# additionalShield.net
KiCad netlist of a schematic drawn in EAGLE
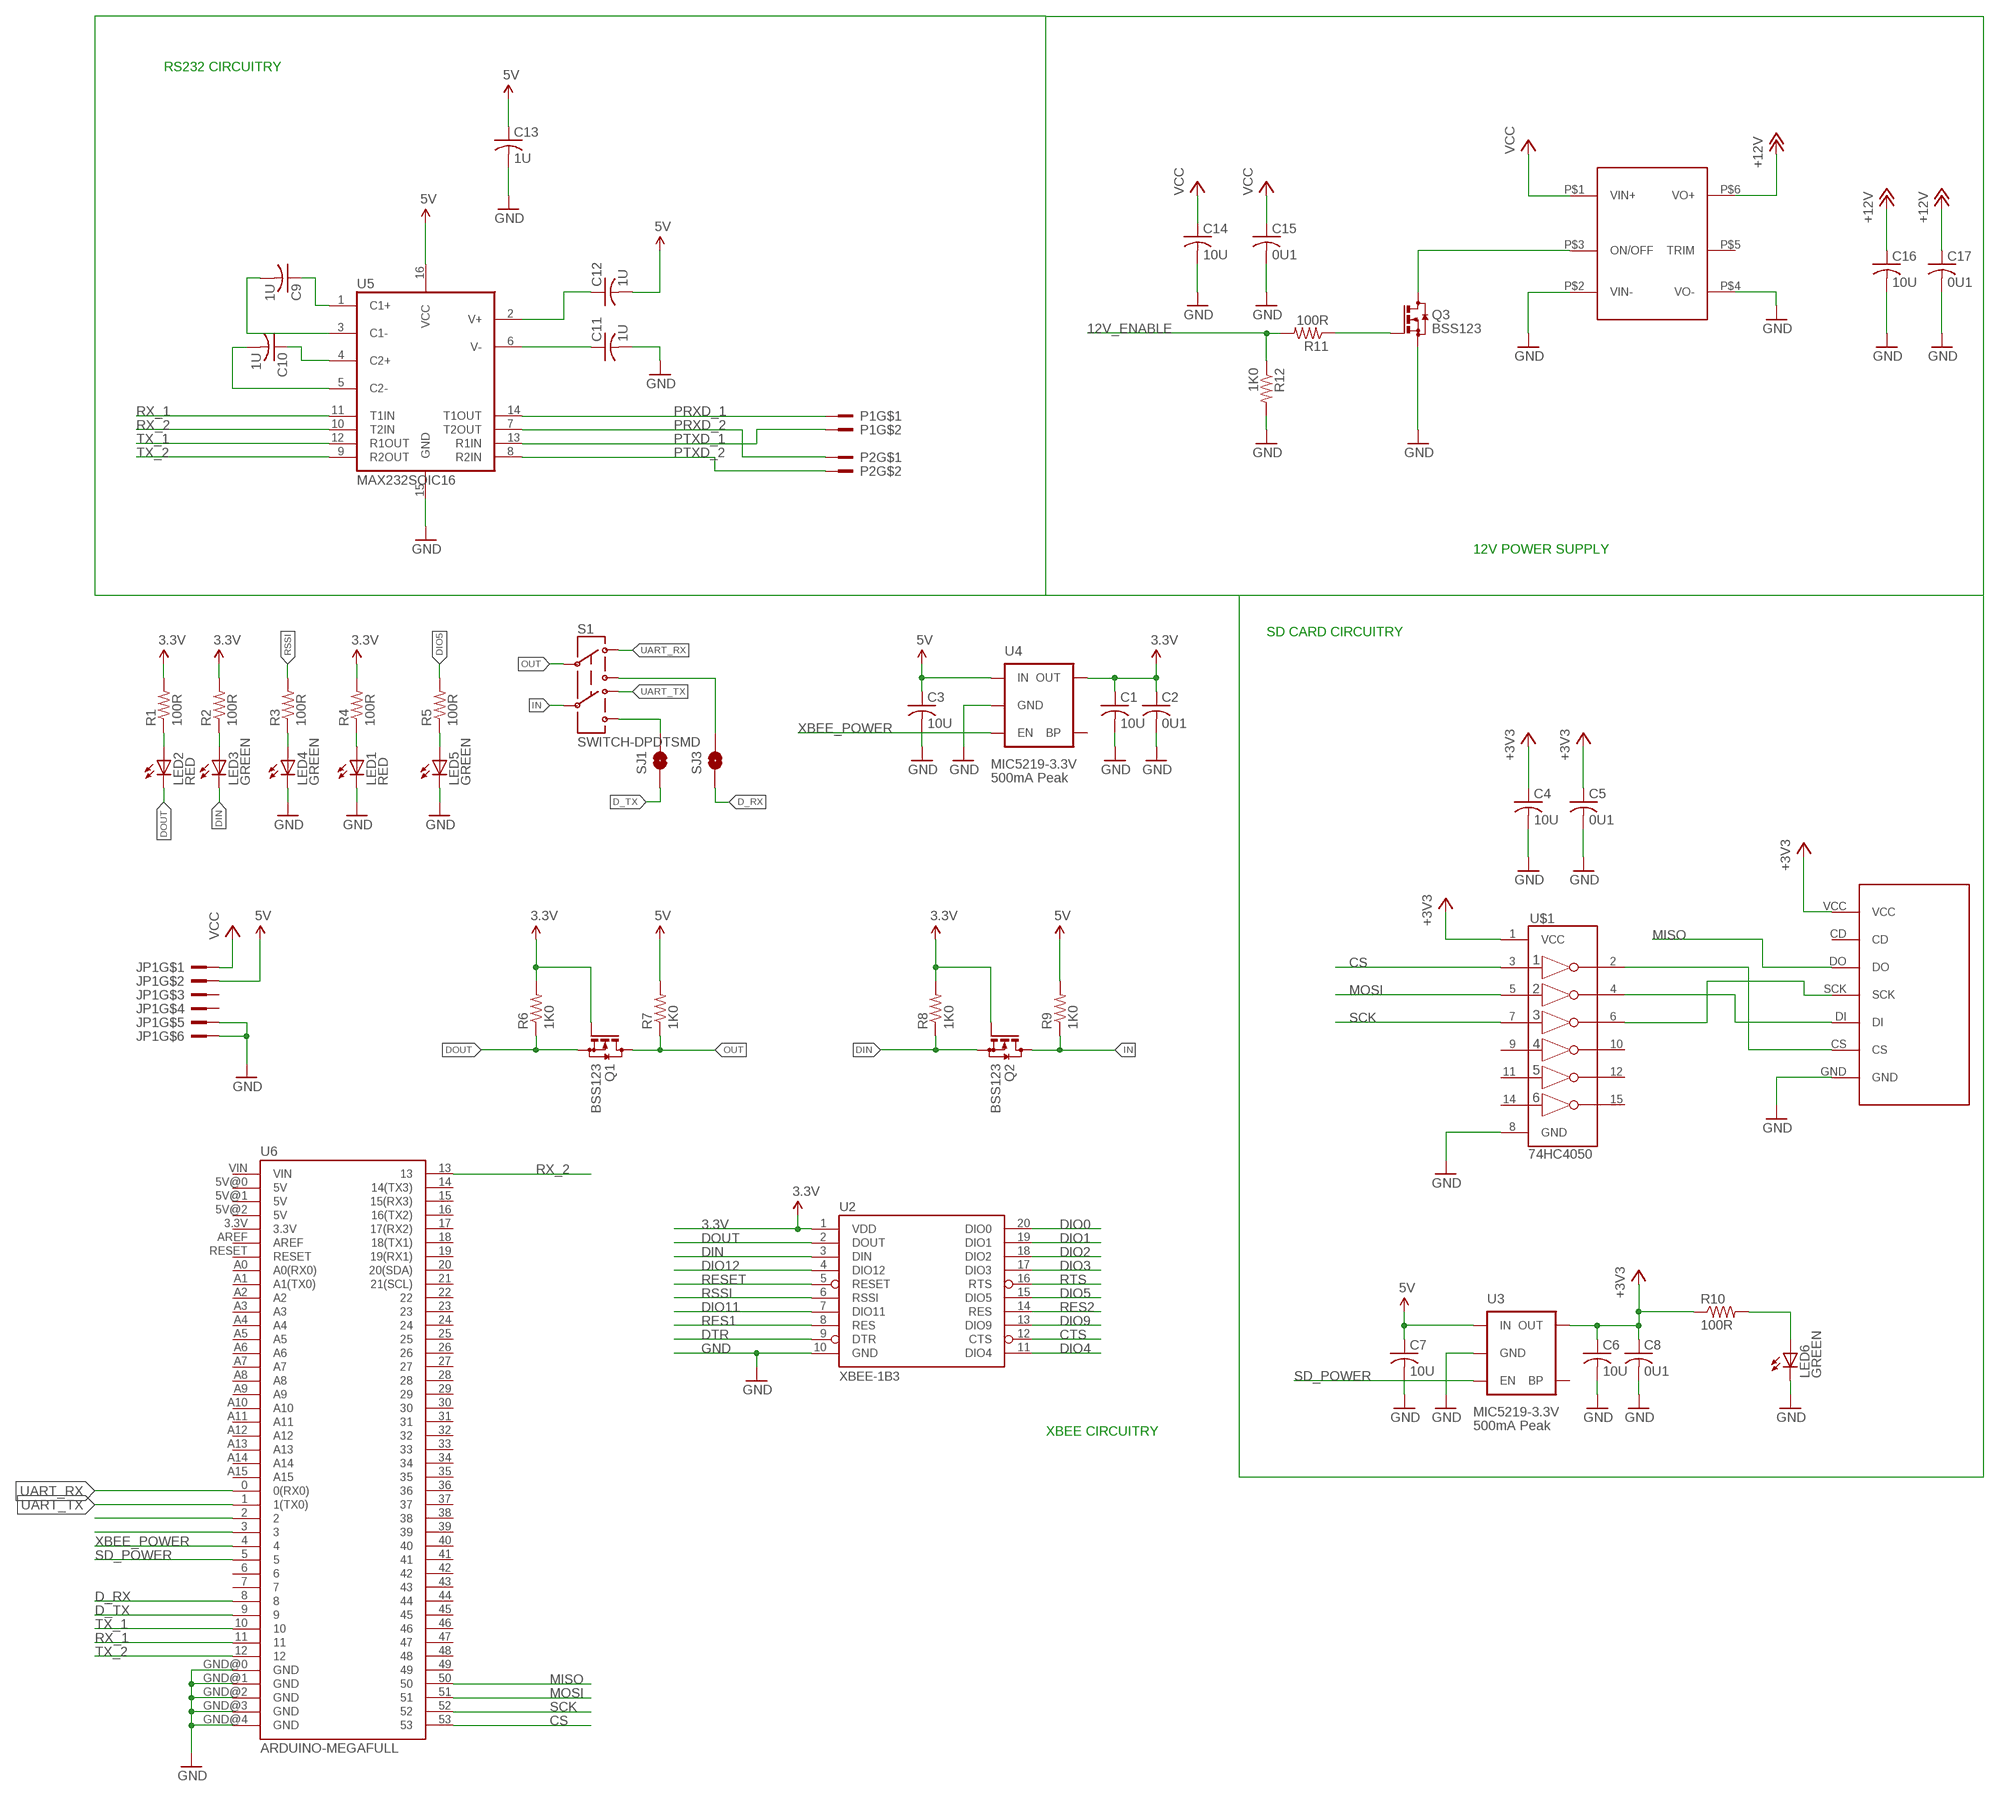
[diagram p0: schematic, sheet 1]

(export (version "E")
  (design (tool "Eeschema 10.0.6"))
  (components
    (comp (ref "C1")
      (value "10U")
      (footprint "eagle-import:C1210K")
      (libsource (lib "eagle-import") (part "C-USC1210K"))
    )
    (comp (ref "C2")
      (value "0U1")
      (footprint "eagle-import:C1210K")
      (libsource (lib "eagle-import") (part "C-USC1210K"))
    )
    (comp (ref "C3")
      (value "10U")
      (footprint "eagle-import:C1210K")
      (libsource (lib "eagle-import") (part "C-USC1210K"))
    )
    (comp (ref "C4")
      (value "10U")
      (footprint "eagle-import:C1210K")
      (libsource (lib "eagle-import") (part "C-USC1210K"))
    )
    (comp (ref "C5")
      (value "0U1")
      (footprint "eagle-import:C1210K")
      (libsource (lib "eagle-import") (part "C-USC1210K"))
    )
    (comp (ref "C6")
      (value "10U")
      (footprint "eagle-import:C1210K")
      (libsource (lib "eagle-import") (part "C-USC1210K"))
    )
    (comp (ref "C7")
      (value "10U")
      (footprint "eagle-import:C1210K")
      (libsource (lib "eagle-import") (part "C-USC1210K"))
    )
    (comp (ref "C8")
      (value "0U1")
      (footprint "eagle-import:C1210K")
      (libsource (lib "eagle-import") (part "C-USC1210K"))
    )
    (comp (ref "C9")
      (value "1U")
      (footprint "eagle-import:C1210K")
      (libsource (lib "eagle-import") (part "C-USC1210K"))
    )
    (comp (ref "C10")
      (value "1U")
      (footprint "eagle-import:C1210K")
      (libsource (lib "eagle-import") (part "C-USC1210K"))
    )
    (comp (ref "C11")
      (value "1U")
      (footprint "eagle-import:C1210K")
      (libsource (lib "eagle-import") (part "C-USC1210K"))
    )
    (comp (ref "C12")
      (value "1U")
      (footprint "eagle-import:C1210K")
      (libsource (lib "eagle-import") (part "C-USC1210K"))
    )
    (comp (ref "C13")
      (value "1U")
      (footprint "eagle-import:C1210K")
      (libsource (lib "eagle-import") (part "C-USC1210K"))
    )
    (comp (ref "C14")
      (value "10U")
      (footprint "eagle-import:C1210K")
      (libsource (lib "eagle-import") (part "C-USC1210K"))
    )
    (comp (ref "C15")
      (value "0U1")
      (footprint "eagle-import:C1210K")
      (libsource (lib "eagle-import") (part "C-USC1210K"))
    )
    (comp (ref "C16")
      (value "10U")
      (footprint "eagle-import:C1210K")
      (libsource (lib "eagle-import") (part "C-USC1210K"))
    )
    (comp (ref "C17")
      (value "0U1")
      (footprint "eagle-import:C1210K")
      (libsource (lib "eagle-import") (part "C-USC1210K"))
    )
    (comp (ref "JP1")
      (value "6PIN2ROWARDUINO")
      (footprint "eagle-import:6PIN2ROWARDUINO")
      (libsource (lib "eagle-import") (part "6PIN2ROWARDUINO"))
    )
    (comp (ref "LED1")
      (value "RED")
      (footprint "eagle-import:CHIPLED_1206")
      (libsource (lib "eagle-import") (part "LEDCHIPLED_1206"))
    )
    (comp (ref "LED2")
      (value "RED")
      (footprint "eagle-import:CHIPLED_1206")
      (libsource (lib "eagle-import") (part "LEDCHIPLED_1206"))
    )
    (comp (ref "LED3")
      (value "GREEN")
      (footprint "eagle-import:CHIPLED_1206")
      (libsource (lib "eagle-import") (part "LEDCHIPLED_1206"))
    )
    (comp (ref "LED4")
      (value "GREEN")
      (footprint "eagle-import:CHIPLED_1206")
      (libsource (lib "eagle-import") (part "LEDCHIPLED_1206"))
    )
    (comp (ref "LED5")
      (value "GREEN")
      (footprint "eagle-import:CHIPLED_1206")
      (libsource (lib "eagle-import") (part "LEDCHIPLED_1206"))
    )
    (comp (ref "LED6")
      (value "GREEN")
      (footprint "eagle-import:CHIPLED_1206")
      (libsource (lib "eagle-import") (part "LEDCHIPLED_1206"))
    )
    (comp (ref "P1")
      (value "DF3A-2P-2DSA")
      (footprint "eagle-import:DF3A-2P-2DSA")
      (libsource (lib "eagle-import") (part "DF3A-2P-2DSA"))
    )
    (comp (ref "P2")
      (value "DF3A-2P-2DSA")
      (footprint "eagle-import:DF3A-2P-2DSA")
      (libsource (lib "eagle-import") (part "DF3A-2P-2DSA"))
    )
    (comp (ref "Q1")
      (value "BSS123")
      (footprint "eagle-import:SOT23")
      (libsource (lib "eagle-import") (part "BSS123"))
    )
    (comp (ref "Q2")
      (value "BSS123")
      (footprint "eagle-import:SOT23")
      (libsource (lib "eagle-import") (part "BSS123"))
    )
    (comp (ref "Q3")
      (value "BSS123")
      (footprint "eagle-import:SOT23")
      (libsource (lib "eagle-import") (part "BSS123"))
    )
    (comp (ref "R1")
      (value "100R")
      (footprint "eagle-import:R1206")
      (libsource (lib "eagle-import") (part "R-US_R1206"))
    )
    (comp (ref "R2")
      (value "100R")
      (footprint "eagle-import:R1206")
      (libsource (lib "eagle-import") (part "R-US_R1206"))
    )
    (comp (ref "R3")
      (value "100R")
      (footprint "eagle-import:R1206")
      (libsource (lib "eagle-import") (part "R-US_R1206"))
    )
    (comp (ref "R4")
      (value "100R")
      (footprint "eagle-import:R1206")
      (libsource (lib "eagle-import") (part "R-US_R1206"))
    )
    (comp (ref "R5")
      (value "100R")
      (footprint "eagle-import:R1206")
      (libsource (lib "eagle-import") (part "R-US_R1206"))
    )
    (comp (ref "R6")
      (value "1K0")
      (footprint "eagle-import:R1206")
      (libsource (lib "eagle-import") (part "R-US_R1206"))
    )
    (comp (ref "R7")
      (value "1K0")
      (footprint "eagle-import:R1206")
      (libsource (lib "eagle-import") (part "R-US_R1206"))
    )
    (comp (ref "R8")
      (value "1K0")
      (footprint "eagle-import:R1206")
      (libsource (lib "eagle-import") (part "R-US_R1206"))
    )
    (comp (ref "R9")
      (value "1K0")
      (footprint "eagle-import:R1206")
      (libsource (lib "eagle-import") (part "R-US_R1206"))
    )
    (comp (ref "R10")
      (value "100R")
      (footprint "eagle-import:R1206")
      (libsource (lib "eagle-import") (part "R-US_R1206"))
    )
    (comp (ref "R11")
      (value "100R")
      (footprint "eagle-import:R1206")
      (libsource (lib "eagle-import") (part "R-US_R1206"))
    )
    (comp (ref "R12")
      (value "1K0")
      (footprint "eagle-import:R1206")
      (libsource (lib "eagle-import") (part "R-US_R1206"))
    )
    (comp (ref "S1")
      (value "SWITCH-DPDTSMD")
      (footprint "eagle-import:AYZ0202")
      (libsource (lib "eagle-import") (part "SWITCH-DPDTSMD"))
    )
    (comp (ref "SJ1")
      (value "D_TX")
      (footprint "eagle-import:SJ_2S")
      (libsource (lib "eagle-import") (part "SOLDERJUMPERNC"))
    )
    (comp (ref "SJ3")
      (value "D_RX")
      (footprint "eagle-import:SJ_2S")
      (libsource (lib "eagle-import") (part "SOLDERJUMPERNC"))
    )
    (comp (ref "U$1")
      (value "74HC4050")
      (footprint "eagle-import:SO16")
      (libsource (lib "eagle-import") (part "74HC4050"))
    )
    (comp (ref "U$5")
      (value "SD_BREAKOUT")
      (footprint "eagle-import:SD_BREAKOUT")
      (libsource (lib "eagle-import") (part "SD_BREAKOUT"))
    )
    (comp (ref "U$11")
      (value "SHHD001A3B41Z")
      (footprint "eagle-import:SHHD001A3B41Z")
      (libsource (lib "eagle-import") (part "SHHD001A3B41Z"))
    )
    (comp (ref "U2")
      (value "XBEE-1B3")
      (footprint "eagle-import:XBEE-SMD")
      (libsource (lib "eagle-import") (part "XBEE-1B3"))
    )
    (comp (ref "U3")
      (value "V_REG_LDOSMD")
      (footprint "eagle-import:SOT23-5")
      (libsource (lib "eagle-import") (part "V_REG_LDOSMD"))
    )
    (comp (ref "U4")
      (value "V_REG_LDOSMD")
      (footprint "eagle-import:SOT23-5")
      (libsource (lib "eagle-import") (part "V_REG_LDOSMD"))
    )
    (comp (ref "U5")
      (value "MAX232SOIC16")
      (footprint "eagle-import:SO016")
      (libsource (lib "eagle-import") (part "MAX232SOIC16"))
    )
    (comp (ref "U6")
      (value "ARDUINO-MEGAFULL")
      (footprint "eagle-import:ARDUINO_MEGA")
      (libsource (lib "eagle-import") (part "ARDUINO-MEGAFULL"))
    )
  )
  (nets
    (net (code "1") (name "+3V3") (class "Default")
      (node (ref "C4") (pin "1") (pinfunction "1_1") (pintype "passive"))
      (node (ref "C5") (pin "1") (pinfunction "1_1") (pintype "passive"))
      (node (ref "C6") (pin "1") (pinfunction "1_1") (pintype "passive"))
      (node (ref "C8") (pin "1") (pinfunction "1_1") (pintype "passive"))
      (node (ref "R10") (pin "1") (pinfunction "1_1") (pintype "passive"))
      (node (ref "U$1") (pin "1") (pinfunction "VCC_1") (pintype "power_in"))
      (node (ref "U$5") (pin "VCC") (pinfunction "VCC_VCC") (pintype "bidirectional"))
      (node (ref "U3") (pin "5") (pinfunction "OUT_5") (pintype "passive"))
    )
    (net (code "2") (name "+12V") (class "Default")
      (node (ref "C16") (pin "1") (pinfunction "1_1") (pintype "passive"))
      (node (ref "C17") (pin "1") (pinfunction "1_1") (pintype "passive"))
      (node (ref "U$11") (pin "P$6") (pinfunction "VO+_P$6") (pintype "bidirectional"))
    )
    (net (code "3") (name "/12V_ENABLE") (class "Default")
      (node (ref "R11") (pin "2") (pinfunction "2_2") (pintype "passive"))
      (node (ref "R12") (pin "1") (pinfunction "1_1") (pintype "passive"))
    )
    (net (code "4") (name "/CS") (class "Default")
      (node (ref "U$1") (pin "3") (pinfunction "1A_3") (pintype "input"))
      (node (ref "U6") (pin "53") (pinfunction "53_53") (pintype "bidirectional"))
    )
    (net (code "5") (name "/CTS") (class "Default")
      (node (ref "U2") (pin "12") (pinfunction "CTS_12") (pintype "output"))
    )
    (net (code "6") (name "/DIO0") (class "Default")
      (node (ref "U2") (pin "20") (pinfunction "DIO0_20") (pintype "bidirectional"))
    )
    (net (code "7") (name "/DIO1") (class "Default")
      (node (ref "U2") (pin "19") (pinfunction "DIO1_19") (pintype "bidirectional"))
    )
    (net (code "8") (name "/DIO2") (class "Default")
      (node (ref "U2") (pin "18") (pinfunction "DIO2_18") (pintype "bidirectional"))
    )
    (net (code "9") (name "/DIO3") (class "Default")
      (node (ref "U2") (pin "17") (pinfunction "DIO3_17") (pintype "bidirectional"))
    )
    (net (code "10") (name "/DIO4") (class "Default")
      (node (ref "U2") (pin "11") (pinfunction "DIO4_11") (pintype "bidirectional"))
    )
    (net (code "11") (name "/DIO9") (class "Default")
      (node (ref "U2") (pin "13") (pinfunction "DIO9_13") (pintype "bidirectional"))
    )
    (net (code "12") (name "/DIO11") (class "Default")
      (node (ref "U2") (pin "7") (pinfunction "DIO11_7") (pintype "bidirectional"))
    )
    (net (code "13") (name "/DIO12") (class "Default")
      (node (ref "U2") (pin "4") (pinfunction "DIO12_4") (pintype "bidirectional"))
    )
    (net (code "14") (name "/DTR") (class "Default")
      (node (ref "U2") (pin "9") (pinfunction "DTR_9") (pintype "bidirectional"))
    )
    (net (code "15") (name "/MISO") (class "Default")
      (node (ref "U$5") (pin "DO") (pinfunction "DO_DO") (pintype "bidirectional"))
      (node (ref "U6") (pin "50") (pinfunction "50_50") (pintype "bidirectional"))
    )
    (net (code "16") (name "/MOSI") (class "Default")
      (node (ref "U$1") (pin "5") (pinfunction "2A_5") (pintype "input"))
      (node (ref "U6") (pin "51") (pinfunction "51_51") (pintype "bidirectional"))
    )
    (net (code "17") (name "/PRXD_1") (class "Default")
      (node (ref "P1") (pin "P$1") (pinfunction "KL_P$1") (pintype "passive"))
      (node (ref "U5") (pin "14") (pinfunction "T1OUT_14") (pintype "output"))
    )
    (net (code "18") (name "/PRXD_2") (class "Default")
      (node (ref "P2") (pin "P$1") (pinfunction "KL_P$1") (pintype "passive"))
      (node (ref "U5") (pin "7") (pinfunction "T2OUT_7") (pintype "output"))
    )
    (net (code "19") (name "/PTXD_1") (class "Default")
      (node (ref "P1") (pin "P$2") (pinfunction "KL_P$2") (pintype "passive"))
      (node (ref "U5") (pin "13") (pinfunction "R1IN_13") (pintype "input"))
    )
    (net (code "20") (name "/PTXD_2") (class "Default")
      (node (ref "P2") (pin "P$2") (pinfunction "KL_P$2") (pintype "passive"))
      (node (ref "U5") (pin "8") (pinfunction "R2IN_8") (pintype "input"))
    )
    (net (code "21") (name "/RES1") (class "Default")
      (node (ref "U2") (pin "8") (pinfunction "RES_8") (pintype "bidirectional"))
    )
    (net (code "22") (name "/RES2") (class "Default")
      (node (ref "U2") (pin "14") (pinfunction "RES_14") (pintype "bidirectional"))
    )
    (net (code "23") (name "/RESET") (class "Default")
      (node (ref "U2") (pin "5") (pinfunction "RESET_5") (pintype "input"))
    )
    (net (code "24") (name "/RTS") (class "Default")
      (node (ref "U2") (pin "16") (pinfunction "RTS_16") (pintype "input"))
    )
    (net (code "25") (name "/RX_1") (class "Default")
      (node (ref "U5") (pin "11") (pinfunction "T1IN_11") (pintype "input"))
      (node (ref "U6") (pin "11") (pinfunction "11_11") (pintype "bidirectional"))
    )
    (net (code "26") (name "/RX_2") (class "Default")
      (node (ref "U5") (pin "10") (pinfunction "T2IN_10") (pintype "input"))
      (node (ref "U6") (pin "13") (pinfunction "13_13") (pintype "bidirectional"))
    )
    (net (code "27") (name "/SCK") (class "Default")
      (node (ref "U$1") (pin "7") (pinfunction "3A_7") (pintype "input"))
      (node (ref "U6") (pin "52") (pinfunction "52_52") (pintype "bidirectional"))
    )
    (net (code "28") (name "/SD_POWER") (class "Default")
      (node (ref "U3") (pin "3") (pinfunction "EN_3") (pintype "input"))
      (node (ref "U6") (pin "5") (pinfunction "5_5") (pintype "bidirectional"))
    )
    (net (code "29") (name "/TX_1") (class "Default")
      (node (ref "U5") (pin "12") (pinfunction "R1OUT_12") (pintype "output"))
      (node (ref "U6") (pin "10") (pinfunction "10_10") (pintype "bidirectional"))
    )
    (net (code "30") (name "/TX_2") (class "Default")
      (node (ref "U5") (pin "9") (pinfunction "R2OUT_9") (pintype "output"))
      (node (ref "U6") (pin "12") (pinfunction "12_12") (pintype "bidirectional"))
    )
    (net (code "31") (name "/XBEE_POWER") (class "Default")
      (node (ref "U4") (pin "3") (pinfunction "EN_3") (pintype "input"))
      (node (ref "U6") (pin "4") (pinfunction "4_4") (pintype "bidirectional"))
    )
    (net (code "32") (name "3.3V") (class "Default")
      (node (ref "C1") (pin "1") (pinfunction "1_1") (pintype "passive"))
      (node (ref "C2") (pin "1") (pinfunction "1_1") (pintype "passive"))
      (node (ref "Q1") (pin "1") (pinfunction "G_1") (pintype "passive"))
      (node (ref "Q2") (pin "1") (pinfunction "G_1") (pintype "passive"))
      (node (ref "R1") (pin "2") (pinfunction "2_2") (pintype "passive"))
      (node (ref "R2") (pin "2") (pinfunction "2_2") (pintype "passive"))
      (node (ref "R4") (pin "2") (pinfunction "2_2") (pintype "passive"))
      (node (ref "R6") (pin "2") (pinfunction "2_2") (pintype "passive"))
      (node (ref "R8") (pin "2") (pinfunction "2_2") (pintype "passive"))
      (node (ref "U2") (pin "1") (pinfunction "VDD_1") (pintype "power_in"))
      (node (ref "U4") (pin "5") (pinfunction "OUT_5") (pintype "passive"))
    )
    (net (code "33") (name "5V") (class "Default")
      (node (ref "C12") (pin "2") (pinfunction "2_2") (pintype "passive"))
      (node (ref "C13") (pin "1") (pinfunction "1_1") (pintype "passive"))
      (node (ref "C3") (pin "1") (pinfunction "1_1") (pintype "passive"))
      (node (ref "C7") (pin "1") (pinfunction "1_1") (pintype "passive"))
      (node (ref "JP1") (pin "P$2") (pinfunction "KL_P$2") (pintype "passive"))
      (node (ref "R7") (pin "2") (pinfunction "2_2") (pintype "passive"))
      (node (ref "R9") (pin "2") (pinfunction "2_2") (pintype "passive"))
      (node (ref "U3") (pin "1") (pinfunction "IN_1") (pintype "input"))
      (node (ref "U4") (pin "1") (pinfunction "IN_1") (pintype "input"))
      (node (ref "U5") (pin "16") (pinfunction "VCC_16") (pintype "bidirectional"))
    )
    (net (code "34") (name "DIN") (class "Default")
      (node (ref "LED3") (pin "C") (pinfunction "C_C") (pintype "passive"))
      (node (ref "Q2") (pin "2") (pinfunction "S_2") (pintype "passive"))
      (node (ref "R8") (pin "1") (pinfunction "1_1") (pintype "passive"))
      (node (ref "U2") (pin "3") (pinfunction "DIN_3") (pintype "input"))
    )
    (net (code "35") (name "DIO5") (class "Default")
      (node (ref "R5") (pin "2") (pinfunction "2_2") (pintype "passive"))
      (node (ref "U2") (pin "15") (pinfunction "DIO5_15") (pintype "bidirectional"))
    )
    (net (code "36") (name "DOUT") (class "Default")
      (node (ref "LED2") (pin "C") (pinfunction "C_C") (pintype "passive"))
      (node (ref "Q1") (pin "2") (pinfunction "S_2") (pintype "passive"))
      (node (ref "R6") (pin "1") (pinfunction "1_1") (pintype "passive"))
      (node (ref "U2") (pin "2") (pinfunction "DOUT_2") (pintype "output"))
    )
    (net (code "37") (name "D_RX") (class "Default")
      (node (ref "SJ3") (pin "1") (pinfunction "1_1") (pintype "passive"))
      (node (ref "U6") (pin "8") (pinfunction "8_8") (pintype "bidirectional"))
    )
    (net (code "38") (name "D_TX") (class "Default")
      (node (ref "SJ1") (pin "1") (pinfunction "1_1") (pintype "passive"))
      (node (ref "U6") (pin "9") (pinfunction "9_9") (pintype "bidirectional"))
    )
    (net (code "39") (name "GND") (class "Default")
      (node (ref "C1") (pin "2") (pinfunction "2_2") (pintype "passive"))
      (node (ref "C11") (pin "2") (pinfunction "2_2") (pintype "passive"))
      (node (ref "C13") (pin "2") (pinfunction "2_2") (pintype "passive"))
      (node (ref "C14") (pin "2") (pinfunction "2_2") (pintype "passive"))
      (node (ref "C15") (pin "2") (pinfunction "2_2") (pintype "passive"))
      (node (ref "C16") (pin "2") (pinfunction "2_2") (pintype "passive"))
      (node (ref "C17") (pin "2") (pinfunction "2_2") (pintype "passive"))
      (node (ref "C2") (pin "2") (pinfunction "2_2") (pintype "passive"))
      (node (ref "C3") (pin "2") (pinfunction "2_2") (pintype "passive"))
      (node (ref "C4") (pin "2") (pinfunction "2_2") (pintype "passive"))
      (node (ref "C5") (pin "2") (pinfunction "2_2") (pintype "passive"))
      (node (ref "C6") (pin "2") (pinfunction "2_2") (pintype "passive"))
      (node (ref "C7") (pin "2") (pinfunction "2_2") (pintype "passive"))
      (node (ref "C8") (pin "2") (pinfunction "2_2") (pintype "passive"))
      (node (ref "JP1") (pin "P$5") (pinfunction "KL_P$5") (pintype "passive"))
      (node (ref "JP1") (pin "P$6") (pinfunction "KL_P$6") (pintype "passive"))
      (node (ref "LED1") (pin "C") (pinfunction "C_C") (pintype "passive"))
      (node (ref "LED4") (pin "C") (pinfunction "C_C") (pintype "passive"))
      (node (ref "LED5") (pin "C") (pinfunction "C_C") (pintype "passive"))
      (node (ref "LED6") (pin "C") (pinfunction "C_C") (pintype "passive"))
      (node (ref "Q3") (pin "2") (pinfunction "S_2") (pintype "passive"))
      (node (ref "R12") (pin "2") (pinfunction "2_2") (pintype "passive"))
      (node (ref "U$1") (pin "8") (pinfunction "GND_8") (pintype "power_in"))
      (node (ref "U$11") (pin "P$2") (pinfunction "VIN-_P$2") (pintype "bidirectional"))
      (node (ref "U$11") (pin "P$4") (pinfunction "VO-_P$4") (pintype "bidirectional"))
      (node (ref "U$5") (pin "GND") (pinfunction "GND_GND") (pintype "bidirectional"))
      (node (ref "U2") (pin "10") (pinfunction "GND_10") (pintype "power_in"))
      (node (ref "U3") (pin "2") (pinfunction "GND_2") (pintype "input"))
      (node (ref "U4") (pin "2") (pinfunction "GND_2") (pintype "input"))
      (node (ref "U5") (pin "15") (pinfunction "GND_15") (pintype "bidirectional"))
      (node (ref "U6") (pin "GND@0") (pinfunction "GND_GND@0") (pintype "bidirectional"))
      (node (ref "U6") (pin "GND@1") (pinfunction "GND_GND@1") (pintype "bidirectional"))
      (node (ref "U6") (pin "GND@2") (pinfunction "GND_GND@2") (pintype "bidirectional"))
      (node (ref "U6") (pin "GND@3") (pinfunction "GND_GND@3") (pintype "bidirectional"))
      (node (ref "U6") (pin "GND@4") (pinfunction "GND_GND@4") (pintype "bidirectional"))
    )
    (net (code "40") (name "IN") (class "Default")
      (node (ref "Q2") (pin "3") (pinfunction "D_3") (pintype "passive"))
      (node (ref "R9") (pin "1") (pinfunction "1_1") (pintype "passive"))
      (node (ref "S1") (pin "5") (pinfunction "5_5") (pintype "bidirectional"))
    )
    (net (code "41") (name "Net-(LED1-PadA)") (class "Default")
      (node (ref "LED1") (pin "A") (pinfunction "A_A") (pintype "passive"))
      (node (ref "R4") (pin "1") (pinfunction "1_1") (pintype "passive"))
    )
    (net (code "42") (name "Net-(LED2-PadA)") (class "Default")
      (node (ref "LED2") (pin "A") (pinfunction "A_A") (pintype "passive"))
      (node (ref "R1") (pin "1") (pinfunction "1_1") (pintype "passive"))
    )
    (net (code "43") (name "Net-(LED3-PadA)") (class "Default")
      (node (ref "LED3") (pin "A") (pinfunction "A_A") (pintype "passive"))
      (node (ref "R2") (pin "1") (pinfunction "1_1") (pintype "passive"))
    )
    (net (code "44") (name "Net-(LED4-PadA)") (class "Default")
      (node (ref "LED4") (pin "A") (pinfunction "A_A") (pintype "passive"))
      (node (ref "R3") (pin "1") (pinfunction "1_1") (pintype "passive"))
    )
    (net (code "45") (name "Net-(LED5-PadA)") (class "Default")
      (node (ref "LED5") (pin "A") (pinfunction "A_A") (pintype "passive"))
      (node (ref "R5") (pin "1") (pinfunction "1_1") (pintype "passive"))
    )
    (net (code "46") (name "Net-(LED6-PadA)") (class "Default")
      (node (ref "LED6") (pin "A") (pinfunction "A_A") (pintype "passive"))
      (node (ref "R10") (pin "2") (pinfunction "2_2") (pintype "passive"))
    )
    (net (code "47") (name "Net-(Q3-D)") (class "Default")
      (node (ref "Q3") (pin "3") (pinfunction "D_3") (pintype "passive"))
      (node (ref "U$11") (pin "P$3") (pinfunction "ON/OFF_P$3") (pintype "bidirectional"))
    )
    (net (code "48") (name "Net-(Q3-G)") (class "Default")
      (node (ref "Q3") (pin "1") (pinfunction "G_1") (pintype "passive"))
      (node (ref "R11") (pin "1") (pinfunction "1_1") (pintype "passive"))
    )
    (net (code "49") (name "Net-(S1-Pad3)") (class "Default")
      (node (ref "S1") (pin "3") (pinfunction "3_3") (pintype "bidirectional"))
      (node (ref "SJ3") (pin "2") (pinfunction "2_2") (pintype "passive"))
    )
    (net (code "50") (name "Net-(S1-Pad6)") (class "Default")
      (node (ref "S1") (pin "6") (pinfunction "6_6") (pintype "bidirectional"))
      (node (ref "SJ1") (pin "2") (pinfunction "2_2") (pintype "passive"))
    )
    (net (code "51") (name "Net-(U$1-1Y)") (class "Default")
      (node (ref "U$1") (pin "2") (pinfunction "1Y_2") (pintype "output"))
      (node (ref "U$5") (pin "CS") (pinfunction "CS_CS") (pintype "bidirectional"))
    )
    (net (code "52") (name "Net-(U$1-2Y)") (class "Default")
      (node (ref "U$1") (pin "4") (pinfunction "2Y_4") (pintype "output"))
      (node (ref "U$5") (pin "DI") (pinfunction "DI_DI") (pintype "bidirectional"))
    )
    (net (code "53") (name "Net-(U$1-3Y)") (class "Default")
      (node (ref "U$1") (pin "6") (pinfunction "3Y_6") (pintype "output"))
      (node (ref "U$5") (pin "SCK") (pinfunction "SCK_SCK") (pintype "bidirectional"))
    )
    (net (code "54") (name "Net-(U5-C1+)") (class "Default")
      (node (ref "C9") (pin "1") (pinfunction "1_1") (pintype "passive"))
      (node (ref "U5") (pin "1") (pinfunction "C1+_1") (pintype "bidirectional"))
    )
    (net (code "55") (name "Net-(U5-C1-)") (class "Default")
      (node (ref "C9") (pin "2") (pinfunction "2_2") (pintype "passive"))
      (node (ref "U5") (pin "3") (pinfunction "C1-_3") (pintype "bidirectional"))
    )
    (net (code "56") (name "Net-(U5-C2+)") (class "Default")
      (node (ref "C10") (pin "1") (pinfunction "1_1") (pintype "passive"))
      (node (ref "U5") (pin "4") (pinfunction "C2+_4") (pintype "bidirectional"))
    )
    (net (code "57") (name "Net-(U5-C2-)") (class "Default")
      (node (ref "C10") (pin "2") (pinfunction "2_2") (pintype "passive"))
      (node (ref "U5") (pin "5") (pinfunction "C2-_5") (pintype "bidirectional"))
    )
    (net (code "58") (name "Net-(U5-V+)") (class "Default")
      (node (ref "C12") (pin "1") (pinfunction "1_1") (pintype "passive"))
      (node (ref "U5") (pin "2") (pinfunction "V+_2") (pintype "bidirectional"))
    )
    (net (code "59") (name "Net-(U5-V-)") (class "Default")
      (node (ref "C11") (pin "1") (pinfunction "1_1") (pintype "passive"))
      (node (ref "U5") (pin "6") (pinfunction "V-_6") (pintype "bidirectional"))
    )
    (net (code "60") (name "OUT") (class "Default")
      (node (ref "Q1") (pin "3") (pinfunction "D_3") (pintype "passive"))
      (node (ref "R7") (pin "1") (pinfunction "1_1") (pintype "passive"))
      (node (ref "S1") (pin "2") (pinfunction "2_2") (pintype "bidirectional"))
    )
    (net (code "61") (name "RSSI") (class "Default")
      (node (ref "R3") (pin "2") (pinfunction "2_2") (pintype "passive"))
      (node (ref "U2") (pin "6") (pinfunction "RSSI_6") (pintype "bidirectional"))
    )
    (net (code "62") (name "UART_RX") (class "Default")
      (node (ref "S1") (pin "1") (pinfunction "1_1") (pintype "bidirectional"))
      (node (ref "U6") (pin "0") (pinfunction "0(RX0)_0") (pintype "bidirectional"))
    )
    (net (code "63") (name "UART_TX") (class "Default")
      (node (ref "S1") (pin "4") (pinfunction "4_4") (pintype "bidirectional"))
      (node (ref "U6") (pin "1") (pinfunction "1(TX0)_1") (pintype "bidirectional"))
    )
    (net (code "64") (name "VCC") (class "Default")
      (node (ref "C14") (pin "1") (pinfunction "1_1") (pintype "passive"))
      (node (ref "C15") (pin "1") (pinfunction "1_1") (pintype "passive"))
      (node (ref "JP1") (pin "P$1") (pinfunction "KL_P$1") (pintype "passive"))
      (node (ref "U$11") (pin "P$1") (pinfunction "VIN+_P$1") (pintype "bidirectional"))
    )
    (net (code "65") (name "unconnected-(JP1C-KL-PadP$3)") (class "Default")
      (node (ref "JP1") (pin "P$3") (pinfunction "KL_P$3") (pintype "passive"))
    )
    (net (code "66") (name "unconnected-(JP1D-KL-PadP$4)") (class "Default")
      (node (ref "JP1") (pin "P$4") (pinfunction "KL_P$4") (pintype "passive"))
    )
    (net (code "67") (name "unconnected-(U$1-4A-Pad9)") (class "Default")
      (node (ref "U$1") (pin "9") (pinfunction "4A_9") (pintype "input"))
    )
    (net (code "68") (name "unconnected-(U$1-4Y-Pad10)") (class "Default")
      (node (ref "U$1") (pin "10") (pinfunction "4Y_10") (pintype "output"))
    )
    (net (code "69") (name "unconnected-(U$1-5A-Pad11)") (class "Default")
      (node (ref "U$1") (pin "11") (pinfunction "5A_11") (pintype "input"))
    )
    (net (code "70") (name "unconnected-(U$1-5Y-Pad12)") (class "Default")
      (node (ref "U$1") (pin "12") (pinfunction "5Y_12") (pintype "output"))
    )
    (net (code "71") (name "unconnected-(U$1-6A-Pad14)") (class "Default")
      (node (ref "U$1") (pin "14") (pinfunction "6A_14") (pintype "input"))
    )
    (net (code "72") (name "unconnected-(U$1-6Y-Pad15)") (class "Default")
      (node (ref "U$1") (pin "15") (pinfunction "6Y_15") (pintype "output"))
    )
    (net (code "73") (name "unconnected-(U$5-PadCD)") (class "Default")
      (node (ref "U$5") (pin "CD") (pinfunction "CD_CD") (pintype "bidirectional"))
    )
    (net (code "74") (name "unconnected-(U$11-TRIM-PadP$5)") (class "Default")
      (node (ref "U$11") (pin "P$5") (pinfunction "TRIM_P$5") (pintype "bidirectional"))
    )
    (net (code "75") (name "unconnected-(U3-BP-Pad4)") (class "Default")
      (node (ref "U3") (pin "4") (pinfunction "BP_4") (pintype "input"))
    )
    (net (code "76") (name "unconnected-(U4-BP-Pad4)") (class "Default")
      (node (ref "U4") (pin "4") (pinfunction "BP_4") (pintype "input"))
    )
    (net (code "77") (name "unconnected-(U6-5V-Pad5V@0)") (class "Default")
      (node (ref "U6") (pin "5V@0") (pinfunction "5V_5V@0") (pintype "bidirectional"))
    )
    (net (code "78") (name "unconnected-(U6-5V-Pad5V@1)") (class "Default")
      (node (ref "U6") (pin "5V@1") (pinfunction "5V_5V@1") (pintype "bidirectional"))
    )
    (net (code "79") (name "unconnected-(U6-5V-Pad5V@2)") (class "Default")
      (node (ref "U6") (pin "5V@2") (pinfunction "5V_5V@2") (pintype "bidirectional"))
    )
    (net (code "80") (name "unconnected-(U6-14(TX3)-Pad14)") (class "Default")
      (node (ref "U6") (pin "14") (pinfunction "14(TX3)_14") (pintype "bidirectional"))
    )
    (net (code "81") (name "unconnected-(U6-15(RX3)-Pad15)") (class "Default")
      (node (ref "U6") (pin "15") (pinfunction "15(RX3)_15") (pintype "bidirectional"))
    )
    (net (code "82") (name "unconnected-(U6-16(TX2)-Pad16)") (class "Default")
      (node (ref "U6") (pin "16") (pinfunction "16(TX2)_16") (pintype "bidirectional"))
    )
    (net (code "83") (name "unconnected-(U6-17(RX2)-Pad17)") (class "Default")
      (node (ref "U6") (pin "17") (pinfunction "17(RX2)_17") (pintype "bidirectional"))
    )
    (net (code "84") (name "unconnected-(U6-18(TX1)-Pad18)") (class "Default")
      (node (ref "U6") (pin "18") (pinfunction "18(TX1)_18") (pintype "bidirectional"))
    )
    (net (code "85") (name "unconnected-(U6-19(RX1)-Pad19)") (class "Default")
      (node (ref "U6") (pin "19") (pinfunction "19(RX1)_19") (pintype "bidirectional"))
    )
    (net (code "86") (name "unconnected-(U6-20(SDA)-Pad20)") (class "Default")
      (node (ref "U6") (pin "20") (pinfunction "20(SDA)_20") (pintype "bidirectional"))
    )
    (net (code "87") (name "unconnected-(U6-21(SCL)-Pad21)") (class "Default")
      (node (ref "U6") (pin "21") (pinfunction "21(SCL)_21") (pintype "bidirectional"))
    )
    (net (code "88") (name "unconnected-(U6-A0(RX0)-PadA0)") (class "Default")
      (node (ref "U6") (pin "A0") (pinfunction "A0(RX0)_A0") (pintype "bidirectional"))
    )
    (net (code "89") (name "unconnected-(U6-A1(TX0)-PadA1)") (class "Default")
      (node (ref "U6") (pin "A1") (pinfunction "A1(TX0)_A1") (pintype "bidirectional"))
    )
    (net (code "90") (name "unconnected-(U6-Pad2)") (class "Default")
      (node (ref "U6") (pin "2") (pinfunction "2_2") (pintype "bidirectional"))
    )
    (net (code "91") (name "unconnected-(U6-Pad3)") (class "Default")
      (node (ref "U6") (pin "3") (pinfunction "3_3") (pintype "bidirectional"))
    )
    (net (code "92") (name "unconnected-(U6-Pad3.3V)") (class "Default")
      (node (ref "U6") (pin "3.3V") (pinfunction "3.3V_3.3V") (pintype "bidirectional"))
    )
    (net (code "93") (name "unconnected-(U6-Pad6)") (class "Default")
      (node (ref "U6") (pin "6") (pinfunction "6_6") (pintype "bidirectional"))
    )
    (net (code "94") (name "unconnected-(U6-Pad7)") (class "Default")
      (node (ref "U6") (pin "7") (pinfunction "7_7") (pintype "bidirectional"))
    )
    (net (code "95") (name "unconnected-(U6-Pad22)") (class "Default")
      (node (ref "U6") (pin "22") (pinfunction "22_22") (pintype "bidirectional"))
    )
    (net (code "96") (name "unconnected-(U6-Pad23)") (class "Default")
      (node (ref "U6") (pin "23") (pinfunction "23_23") (pintype "bidirectional"))
    )
    (net (code "97") (name "unconnected-(U6-Pad24)") (class "Default")
      (node (ref "U6") (pin "24") (pinfunction "24_24") (pintype "bidirectional"))
    )
    (net (code "98") (name "unconnected-(U6-Pad25)") (class "Default")
      (node (ref "U6") (pin "25") (pinfunction "25_25") (pintype "bidirectional"))
    )
    (net (code "99") (name "unconnected-(U6-Pad26)") (class "Default")
      (node (ref "U6") (pin "26") (pinfunction "26_26") (pintype "bidirectional"))
    )
    (net (code "100") (name "unconnected-(U6-Pad27)") (class "Default")
      (node (ref "U6") (pin "27") (pinfunction "27_27") (pintype "bidirectional"))
    )
    (net (code "101") (name "unconnected-(U6-Pad28)") (class "Default")
      (node (ref "U6") (pin "28") (pinfunction "28_28") (pintype "bidirectional"))
    )
    (net (code "102") (name "unconnected-(U6-Pad29)") (class "Default")
      (node (ref "U6") (pin "29") (pinfunction "29_29") (pintype "bidirectional"))
    )
    (net (code "103") (name "unconnected-(U6-Pad30)") (class "Default")
      (node (ref "U6") (pin "30") (pinfunction "30_30") (pintype "bidirectional"))
    )
    (net (code "104") (name "unconnected-(U6-Pad31)") (class "Default")
      (node (ref "U6") (pin "31") (pinfunction "31_31") (pintype "bidirectional"))
    )
    (net (code "105") (name "unconnected-(U6-Pad32)") (class "Default")
      (node (ref "U6") (pin "32") (pinfunction "32_32") (pintype "bidirectional"))
    )
    (net (code "106") (name "unconnected-(U6-Pad33)") (class "Default")
      (node (ref "U6") (pin "33") (pinfunction "33_33") (pintype "bidirectional"))
    )
    (net (code "107") (name "unconnected-(U6-Pad34)") (class "Default")
      (node (ref "U6") (pin "34") (pinfunction "34_34") (pintype "bidirectional"))
    )
    (net (code "108") (name "unconnected-(U6-Pad35)") (class "Default")
      (node (ref "U6") (pin "35") (pinfunction "35_35") (pintype "bidirectional"))
    )
    (net (code "109") (name "unconnected-(U6-Pad36)") (class "Default")
      (node (ref "U6") (pin "36") (pinfunction "36_36") (pintype "bidirectional"))
    )
    (net (code "110") (name "unconnected-(U6-Pad37)") (class "Default")
      (node (ref "U6") (pin "37") (pinfunction "37_37") (pintype "bidirectional"))
    )
    (net (code "111") (name "unconnected-(U6-Pad38)") (class "Default")
      (node (ref "U6") (pin "38") (pinfunction "38_38") (pintype "bidirectional"))
    )
    (net (code "112") (name "unconnected-(U6-Pad39)") (class "Default")
      (node (ref "U6") (pin "39") (pinfunction "39_39") (pintype "bidirectional"))
    )
    (net (code "113") (name "unconnected-(U6-Pad40)") (class "Default")
      (node (ref "U6") (pin "40") (pinfunction "40_40") (pintype "bidirectional"))
    )
    (net (code "114") (name "unconnected-(U6-Pad41)") (class "Default")
      (node (ref "U6") (pin "41") (pinfunction "41_41") (pintype "bidirectional"))
    )
    (net (code "115") (name "unconnected-(U6-Pad42)") (class "Default")
      (node (ref "U6") (pin "42") (pinfunction "42_42") (pintype "bidirectional"))
    )
    (net (code "116") (name "unconnected-(U6-Pad43)") (class "Default")
      (node (ref "U6") (pin "43") (pinfunction "43_43") (pintype "bidirectional"))
    )
    (net (code "117") (name "unconnected-(U6-Pad44)") (class "Default")
      (node (ref "U6") (pin "44") (pinfunction "44_44") (pintype "bidirectional"))
    )
    (net (code "118") (name "unconnected-(U6-Pad45)") (class "Default")
      (node (ref "U6") (pin "45") (pinfunction "45_45") (pintype "bidirectional"))
    )
    (net (code "119") (name "unconnected-(U6-Pad46)") (class "Default")
      (node (ref "U6") (pin "46") (pinfunction "46_46") (pintype "bidirectional"))
    )
    (net (code "120") (name "unconnected-(U6-Pad47)") (class "Default")
      (node (ref "U6") (pin "47") (pinfunction "47_47") (pintype "bidirectional"))
    )
    (net (code "121") (name "unconnected-(U6-Pad48)") (class "Default")
      (node (ref "U6") (pin "48") (pinfunction "48_48") (pintype "bidirectional"))
    )
    (net (code "122") (name "unconnected-(U6-Pad49)") (class "Default")
      (node (ref "U6") (pin "49") (pinfunction "49_49") (pintype "bidirectional"))
    )
    (net (code "123") (name "unconnected-(U6-PadA2)") (class "Default")
      (node (ref "U6") (pin "A2") (pinfunction "A2_A2") (pintype "bidirectional"))
    )
    (net (code "124") (name "unconnected-(U6-PadA3)") (class "Default")
      (node (ref "U6") (pin "A3") (pinfunction "A3_A3") (pintype "bidirectional"))
    )
    (net (code "125") (name "unconnected-(U6-PadA4)") (class "Default")
      (node (ref "U6") (pin "A4") (pinfunction "A4_A4") (pintype "bidirectional"))
    )
    (net (code "126") (name "unconnected-(U6-PadA5)") (class "Default")
      (node (ref "U6") (pin "A5") (pinfunction "A5_A5") (pintype "bidirectional"))
    )
    (net (code "127") (name "unconnected-(U6-PadA6)") (class "Default")
      (node (ref "U6") (pin "A6") (pinfunction "A6_A6") (pintype "bidirectional"))
    )
    (net (code "128") (name "unconnected-(U6-PadA7)") (class "Default")
      (node (ref "U6") (pin "A7") (pinfunction "A7_A7") (pintype "bidirectional"))
    )
    (net (code "129") (name "unconnected-(U6-PadA8)") (class "Default")
      (node (ref "U6") (pin "A8") (pinfunction "A8_A8") (pintype "bidirectional"))
    )
    (net (code "130") (name "unconnected-(U6-PadA9)") (class "Default")
      (node (ref "U6") (pin "A9") (pinfunction "A9_A9") (pintype "bidirectional"))
    )
    (net (code "131") (name "unconnected-(U6-PadA10)") (class "Default")
      (node (ref "U6") (pin "A10") (pinfunction "A10_A10") (pintype "bidirectional"))
    )
    (net (code "132") (name "unconnected-(U6-PadA11)") (class "Default")
      (node (ref "U6") (pin "A11") (pinfunction "A11_A11") (pintype "bidirectional"))
    )
    (net (code "133") (name "unconnected-(U6-PadA12)") (class "Default")
      (node (ref "U6") (pin "A12") (pinfunction "A12_A12") (pintype "bidirectional"))
    )
    (net (code "134") (name "unconnected-(U6-PadA13)") (class "Default")
      (node (ref "U6") (pin "A13") (pinfunction "A13_A13") (pintype "bidirectional"))
    )
    (net (code "135") (name "unconnected-(U6-PadA14)") (class "Default")
      (node (ref "U6") (pin "A14") (pinfunction "A14_A14") (pintype "bidirectional"))
    )
    (net (code "136") (name "unconnected-(U6-PadA15)") (class "Default")
      (node (ref "U6") (pin "A15") (pinfunction "A15_A15") (pintype "bidirectional"))
    )
    (net (code "137") (name "unconnected-(U6-PadAREF)") (class "Default")
      (node (ref "U6") (pin "AREF") (pinfunction "AREF_AREF") (pintype "bidirectional"))
    )
    (net (code "138") (name "unconnected-(U6-PadRESET)") (class "Default")
      (node (ref "U6") (pin "RESET") (pinfunction "RESET_RESET") (pintype "bidirectional"))
    )
    (net (code "139") (name "unconnected-(U6-PadVIN)") (class "Default")
      (node (ref "U6") (pin "VIN") (pinfunction "VIN_VIN") (pintype "bidirectional"))
    )
  )
)
